# SparkFun_AST-CAN485.net
KiCad netlist of a schematic drawn in EAGLE
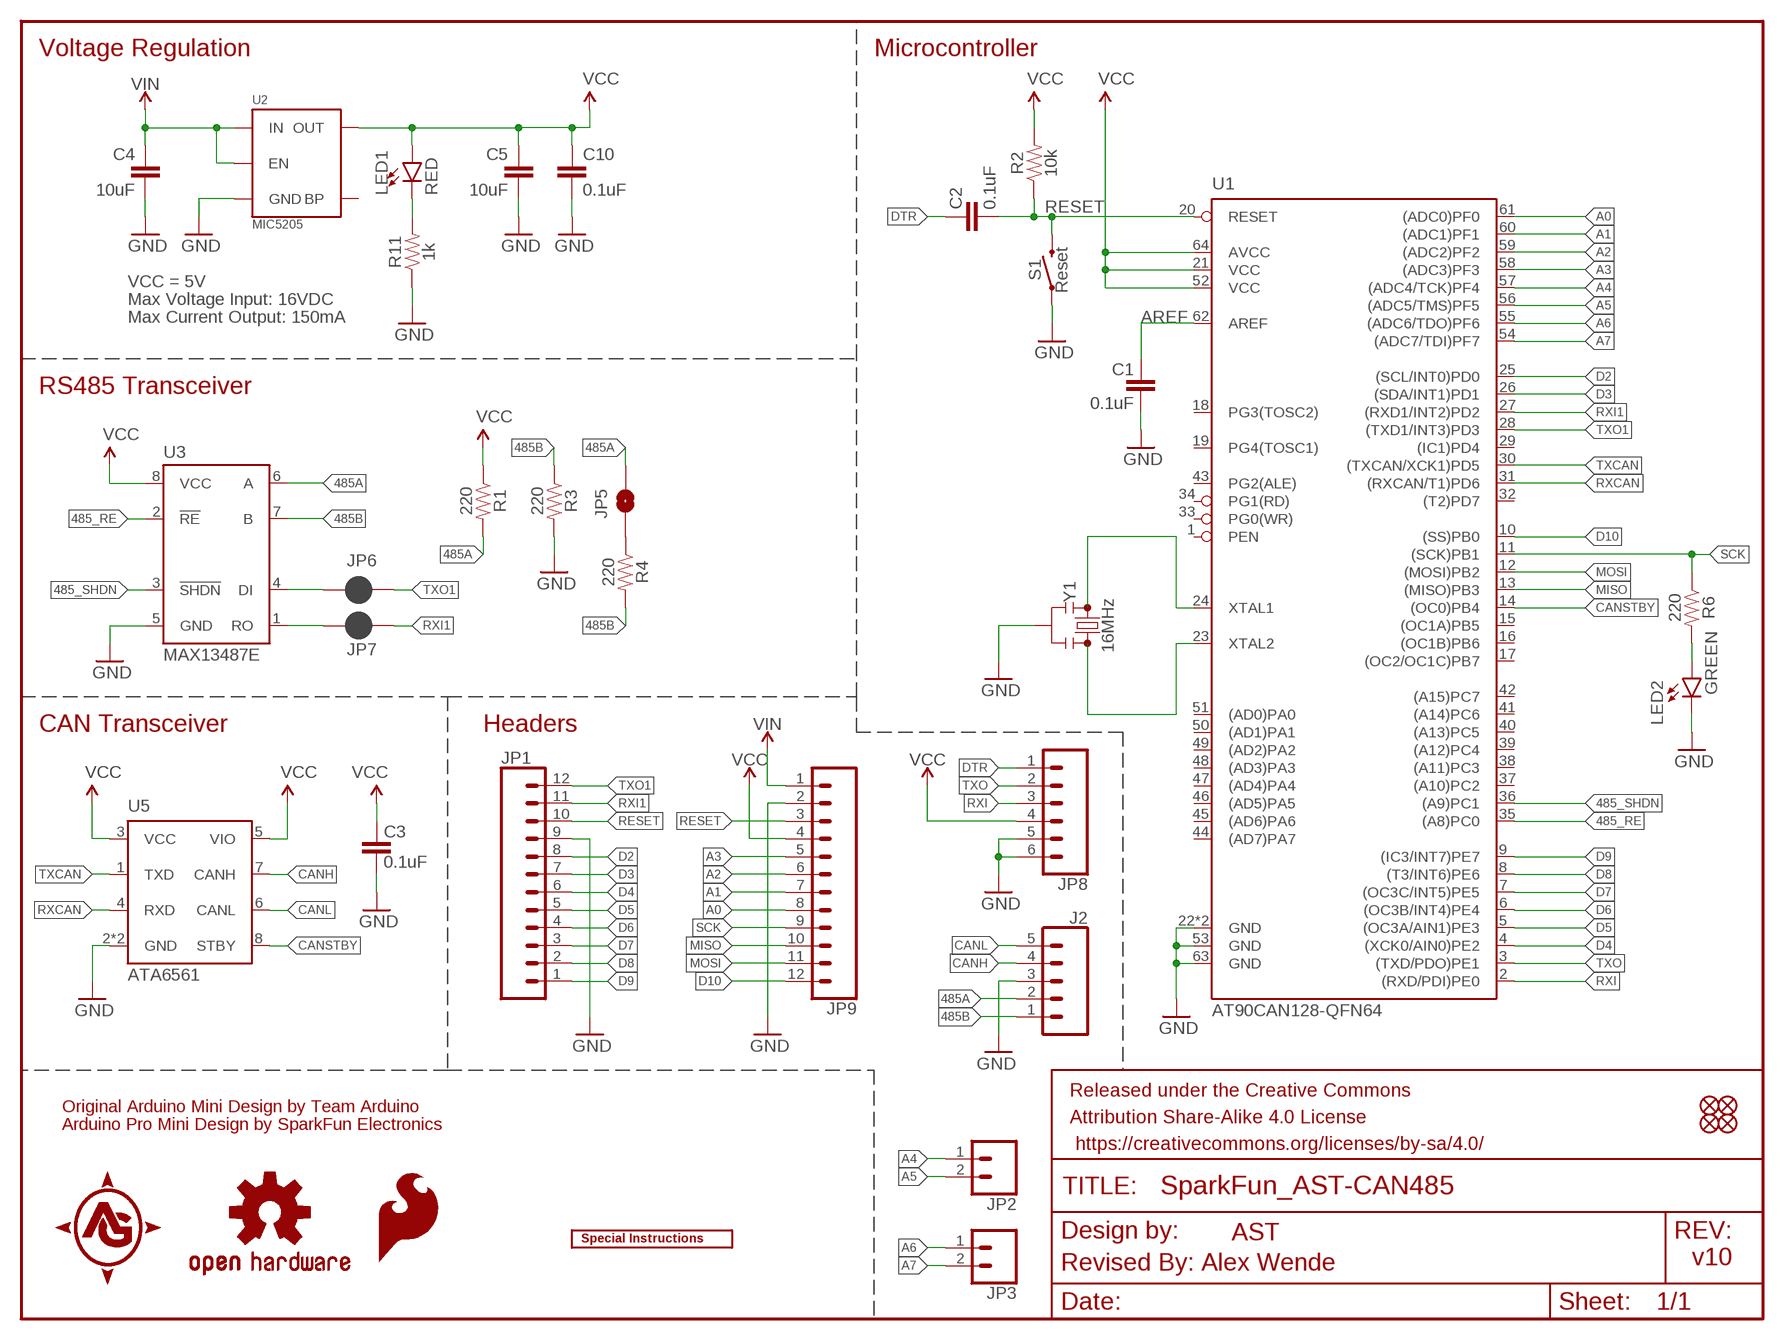
[diagram p0: schematic, sheet 1]

(export (version "E")
  (design (tool "Eeschema 10.0.6"))
  (components
    (comp (ref "C1")
      (value "0.1uF")
      (footprint "eagle-import:0402")
      (libsource (lib "eagle-import") (part "0.1UF-0402-16V-10%"))
    )
    (comp (ref "C2")
      (value "0.1uF")
      (footprint "eagle-import:0402")
      (libsource (lib "eagle-import") (part "0.1UF-0402-16V-10%"))
    )
    (comp (ref "C3")
      (value "0.1uF")
      (footprint "eagle-import:0402")
      (libsource (lib "eagle-import") (part "0.1UF-0402-16V-10%"))
    )
    (comp (ref "C4")
      (value "10uF")
      (footprint "eagle-import:1210")
      (libsource (lib "eagle-import") (part "10UF-1210-50V-20%"))
    )
    (comp (ref "C5")
      (value "10uF")
      (footprint "eagle-import:1210")
      (libsource (lib "eagle-import") (part "10UF-1210-50V-20%"))
    )
    (comp (ref "C10")
      (value "0.1uF")
      (footprint "eagle-import:0402")
      (libsource (lib "eagle-import") (part "0.1UF-0402-16V-10%"))
    )
    (comp (ref "FD1")
      (value "FIDUCIALUFIDUCIAL")
      (footprint "eagle-import:FIDUCIAL-MICRO")
      (libsource (lib "eagle-import") (part "FIDUCIALUFIDUCIAL"))
    )
    (comp (ref "FD2")
      (value "FIDUCIALUFIDUCIAL")
      (footprint "eagle-import:FIDUCIAL-MICRO")
      (libsource (lib "eagle-import") (part "FIDUCIALUFIDUCIAL"))
    )
    (comp (ref "FD3")
      (value "FIDUCIALUFIDUCIAL")
      (footprint "eagle-import:FIDUCIAL-MICRO")
      (libsource (lib "eagle-import") (part "FIDUCIALUFIDUCIAL"))
    )
    (comp (ref "FD4")
      (value "FIDUCIALUFIDUCIAL")
      (footprint "eagle-import:FIDUCIAL-MICRO")
      (libsource (lib "eagle-import") (part "FIDUCIALUFIDUCIAL"))
    )
    (comp (ref "FRAME1")
      (value "FRAME-LETTER")
      (footprint "eagle-import:CREATIVE_COMMONS")
      (libsource (lib "eagle-import") (part "FRAME-LETTER"))
    )
    (comp (ref "J2")
      (value "CONN_05NO_SILK")
      (footprint "eagle-import:1X05_NO_SILK")
      (libsource (lib "eagle-import") (part "CONN_05NO_SILK"))
    )
    (comp (ref "JP1")
      (value "CONN_12NO_SILK")
      (footprint "eagle-import:1X12_NO_SILK")
      (libsource (lib "eagle-import") (part "CONN_12NO_SILK"))
    )
    (comp (ref "JP2")
      (value "CONN_021X02_NO_SILK")
      (footprint "eagle-import:1X02_NO_SILK")
      (libsource (lib "eagle-import") (part "CONN_021X02_NO_SILK"))
    )
    (comp (ref "JP3")
      (value "CONN_021X02_NO_SILK")
      (footprint "eagle-import:1X02_NO_SILK")
      (libsource (lib "eagle-import") (part "CONN_021X02_NO_SILK"))
    )
    (comp (ref "JP5")
      (value "JUMPER-PAD-2-NO")
      (footprint "eagle-import:PAD-JUMPER-2-NO_NO_SILK")
      (libsource (lib "eagle-import") (part "JUMPER-PAD-2-NO"))
    )
    (comp (ref "JP6")
      (value "JUMPER-SMT_2_NC_PASTE_NO-SILK")
      (footprint "eagle-import:SMT-JUMPER_2_NC_PASTE_NO-SILK")
      (libsource (lib "eagle-import") (part "JUMPER-SMT_2_NC_PASTE_NO-SILK"))
    )
    (comp (ref "JP7")
      (value "JUMPER-SMT_2_NC_PASTE_NO-SILK")
      (footprint "eagle-import:SMT-JUMPER_2_NC_PASTE_NO-SILK")
      (libsource (lib "eagle-import") (part "JUMPER-SMT_2_NC_PASTE_NO-SILK"))
    )
    (comp (ref "JP8")
      (value "CONN_06NO_SILK_NO_POP")
      (footprint "eagle-import:1X06_NO_SILK")
      (libsource (lib "eagle-import") (part "CONN_06NO_SILK_NO_POP"))
    )
    (comp (ref "JP9")
      (value "CONN_12NO_SILK")
      (footprint "eagle-import:1X12_NO_SILK")
      (libsource (lib "eagle-import") (part "CONN_12NO_SILK"))
    )
    (comp (ref "LED1")
      (value "RED")
      (footprint "eagle-import:LED-0603")
      (libsource (lib "eagle-import") (part "LED-RED0603"))
    )
    (comp (ref "LED2")
      (value "GREEN")
      (footprint "eagle-import:LED-0603")
      (libsource (lib "eagle-import") (part "LED-GREEN0603"))
    )
    (comp (ref "LOGO1")
      (value "OSHW-LOGOMINI")
      (footprint "eagle-import:OSHW-LOGO-MINI")
      (libsource (lib "eagle-import") (part "OSHW-LOGOMINI"))
    )
    (comp (ref "LOGO2")
      (value "SFE_LOGO_FLAME0.05_INCH")
      (footprint "eagle-import:SFE_LOGO_FLAME_.05")
      (libsource (lib "eagle-import") (part "SFE_LOGO_FLAME0.05_INCH"))
    )
    (comp (ref "R1")
      (value "220")
      (footprint "eagle-import:0603")
      (libsource (lib "eagle-import") (part "220OHM-0603-1/10W-1%"))
    )
    (comp (ref "R2")
      (value "10k")
      (footprint "eagle-import:0603")
      (libsource (lib "eagle-import") (part "10KOHM-0603-1/10W-1%"))
    )
    (comp (ref "R3")
      (value "220")
      (footprint "eagle-import:0603")
      (libsource (lib "eagle-import") (part "220OHM-0603-1/10W-1%"))
    )
    (comp (ref "R4")
      (value "220")
      (footprint "eagle-import:0603")
      (libsource (lib "eagle-import") (part "220OHM-0603-1/10W-1%"))
    )
    (comp (ref "R6")
      (value "220")
      (footprint "eagle-import:0603")
      (libsource (lib "eagle-import") (part "220OHM-0603-1/10W-1%"))
    )
    (comp (ref "R11")
      (value "1k")
      (footprint "eagle-import:0603")
      (libsource (lib "eagle-import") (part "1KOHM-0603-1/10W-1%"))
    )
    (comp (ref "S1")
      (value "Reset")
      (footprint "eagle-import:TACTILE_SWITCH_SMD_4.6X2.8MM")
      (libsource (lib "eagle-import") (part "MOMENTARY-SWITCH-SPST-SMD-4.6X2.8MM"))
    )
    (comp (ref "U$1")
      (value "SPECIAL_INSTRUCTIONS-ORDERING")
      (footprint "eagle-import:ORDERING_INSTRUCTIONS")
      (libsource (lib "eagle-import") (part "SPECIAL_INSTRUCTIONS-ORDERING"))
    )
    (comp (ref "U1")
      (value "AT90CAN128-QFN64")
      (footprint "eagle-import:QFN-64")
      (libsource (lib "eagle-import") (part "AT90CAN128-QFN64"))
    )
    (comp (ref "U2")
      (value "MIC5205")
      (footprint "eagle-import:SOT23-5")
      (libsource (lib "eagle-import") (part "MIC5205"))
    )
    (comp (ref "U3")
      (value "MAX13487E")
      (footprint "eagle-import:SO08")
      (libsource (lib "eagle-import") (part "MAX13487E"))
    )
    (comp (ref "U5")
      (value "ATA6561")
      (footprint "eagle-import:DFN8")
      (libsource (lib "eagle-import") (part "ATA6561"))
    )
    (comp (ref "Y1")
      (value "16MHz")
      (footprint "eagle-import:RESONATOR-SMD-3.2X1.3(SLIM)")
      (libsource (lib "eagle-import") (part "RESONATOR-16MHZSMD_3.2X1.3_SLIM"))
    )
  )
  (nets
    (net (code "1") (name "/AREF") (class "Default")
      (node (ref "C1") (pin "2") (pinfunction "2_2") (pintype "passive"))
      (node (ref "U1") (pin "62") (pinfunction "AREF_62") (pintype "bidirectional"))
    )
    (net (code "2") (name "485A") (class "Default")
      (node (ref "J2") (pin "2") (pinfunction "2_2") (pintype "passive"))
      (node (ref "JP5") (pin "2") (pinfunction "2_2") (pintype "passive"))
      (node (ref "R1") (pin "2") (pinfunction "2_2") (pintype "passive"))
      (node (ref "U3") (pin "6") (pinfunction "A_6") (pintype "bidirectional"))
    )
    (net (code "3") (name "485B") (class "Default")
      (node (ref "J2") (pin "1") (pinfunction "1_1") (pintype "passive"))
      (node (ref "R3") (pin "1") (pinfunction "1_1") (pintype "passive"))
      (node (ref "R4") (pin "2") (pinfunction "2_2") (pintype "passive"))
      (node (ref "U3") (pin "7") (pinfunction "B_7") (pintype "bidirectional"))
    )
    (net (code "4") (name "485_RE") (class "Default")
      (node (ref "U1") (pin "35") (pinfunction "(A8)PC0_35") (pintype "bidirectional"))
      (node (ref "U3") (pin "2") (pinfunction "~{RE}_2") (pintype "bidirectional"))
    )
    (net (code "5") (name "485_SHDN") (class "Default")
      (node (ref "U1") (pin "36") (pinfunction "(A9)PC1_36") (pintype "bidirectional"))
      (node (ref "U3") (pin "3") (pinfunction "~{SHDN}_3") (pintype "bidirectional"))
    )
    (net (code "6") (name "A0") (class "Default")
      (node (ref "JP9") (pin "8") (pinfunction "8_8") (pintype "passive"))
      (node (ref "U1") (pin "61") (pinfunction "(ADC0)PF0_61") (pintype "bidirectional"))
    )
    (net (code "7") (name "A1") (class "Default")
      (node (ref "JP9") (pin "7") (pinfunction "7_7") (pintype "passive"))
      (node (ref "U1") (pin "60") (pinfunction "(ADC1)PF1_60") (pintype "bidirectional"))
    )
    (net (code "8") (name "A2") (class "Default")
      (node (ref "JP9") (pin "6") (pinfunction "6_6") (pintype "passive"))
      (node (ref "U1") (pin "59") (pinfunction "(ADC2)PF2_59") (pintype "bidirectional"))
    )
    (net (code "9") (name "A3") (class "Default")
      (node (ref "JP9") (pin "5") (pinfunction "5_5") (pintype "passive"))
      (node (ref "U1") (pin "58") (pinfunction "(ADC3)PF3_58") (pintype "bidirectional"))
    )
    (net (code "10") (name "A4") (class "Default")
      (node (ref "JP2") (pin "1") (pinfunction "1_1") (pintype "passive"))
      (node (ref "U1") (pin "57") (pinfunction "(ADC4/TCK)PF4_57") (pintype "bidirectional"))
    )
    (net (code "11") (name "A5") (class "Default")
      (node (ref "JP2") (pin "2") (pinfunction "2_2") (pintype "passive"))
      (node (ref "U1") (pin "56") (pinfunction "(ADC5/TMS)PF5_56") (pintype "bidirectional"))
    )
    (net (code "12") (name "A6") (class "Default")
      (node (ref "JP3") (pin "1") (pinfunction "1_1") (pintype "passive"))
      (node (ref "U1") (pin "55") (pinfunction "(ADC6/TDO)PF6_55") (pintype "bidirectional"))
    )
    (net (code "13") (name "A7") (class "Default")
      (node (ref "JP3") (pin "2") (pinfunction "2_2") (pintype "passive"))
      (node (ref "U1") (pin "54") (pinfunction "(ADC7/TDI)PF7_54") (pintype "bidirectional"))
    )
    (net (code "14") (name "CANH") (class "Default")
      (node (ref "J2") (pin "4") (pinfunction "4_4") (pintype "passive"))
      (node (ref "U5") (pin "7") (pinfunction "CANH_7") (pintype "bidirectional"))
    )
    (net (code "15") (name "CANL") (class "Default")
      (node (ref "J2") (pin "5") (pinfunction "5_5") (pintype "passive"))
      (node (ref "U5") (pin "6") (pinfunction "CANL_6") (pintype "bidirectional"))
    )
    (net (code "16") (name "CANSTBY") (class "Default")
      (node (ref "U1") (pin "14") (pinfunction "(OC0)PB4_14") (pintype "bidirectional"))
      (node (ref "U5") (pin "8") (pinfunction "STBY_8") (pintype "bidirectional"))
    )
    (net (code "17") (name "D2") (class "Default")
      (node (ref "JP1") (pin "8") (pinfunction "8_8") (pintype "passive"))
      (node (ref "U1") (pin "25") (pinfunction "(SCL/INT0)PD0_25") (pintype "bidirectional"))
    )
    (net (code "18") (name "D3") (class "Default")
      (node (ref "JP1") (pin "7") (pinfunction "7_7") (pintype "passive"))
      (node (ref "U1") (pin "26") (pinfunction "(SDA/INT1)PD1_26") (pintype "bidirectional"))
    )
    (net (code "19") (name "D4") (class "Default")
      (node (ref "JP1") (pin "6") (pinfunction "6_6") (pintype "passive"))
      (node (ref "U1") (pin "4") (pinfunction "(XCK0/AIN0)PE2_4") (pintype "bidirectional"))
    )
    (net (code "20") (name "D5") (class "Default")
      (node (ref "JP1") (pin "5") (pinfunction "5_5") (pintype "passive"))
      (node (ref "U1") (pin "5") (pinfunction "(OC3A/AIN1)PE3_5") (pintype "bidirectional"))
    )
    (net (code "21") (name "D6") (class "Default")
      (node (ref "JP1") (pin "4") (pinfunction "4_4") (pintype "passive"))
      (node (ref "U1") (pin "6") (pinfunction "(OC3B/INT4)PE4_6") (pintype "bidirectional"))
    )
    (net (code "22") (name "D7") (class "Default")
      (node (ref "JP1") (pin "3") (pinfunction "3_3") (pintype "passive"))
      (node (ref "U1") (pin "7") (pinfunction "(OC3C/INT5)PE5_7") (pintype "bidirectional"))
    )
    (net (code "23") (name "D8") (class "Default")
      (node (ref "JP1") (pin "2") (pinfunction "2_2") (pintype "passive"))
      (node (ref "U1") (pin "8") (pinfunction "(T3/INT6)PE6_8") (pintype "bidirectional"))
    )
    (net (code "24") (name "D9") (class "Default")
      (node (ref "JP1") (pin "1") (pinfunction "1_1") (pintype "passive"))
      (node (ref "U1") (pin "9") (pinfunction "(IC3/INT7)PE7_9") (pintype "bidirectional"))
    )
    (net (code "25") (name "D10") (class "Default")
      (node (ref "JP9") (pin "12") (pinfunction "12_12") (pintype "passive"))
      (node (ref "U1") (pin "10") (pinfunction "(SS)PB0_10") (pintype "bidirectional"))
    )
    (net (code "26") (name "DTR") (class "Default")
      (node (ref "C2") (pin "2") (pinfunction "2_2") (pintype "passive"))
      (node (ref "JP8") (pin "1") (pinfunction "1_1") (pintype "passive"))
    )
    (net (code "27") (name "GND") (class "Default")
      (node (ref "C1") (pin "1") (pinfunction "1_1") (pintype "passive"))
      (node (ref "C10") (pin "2") (pinfunction "2_2") (pintype "passive"))
      (node (ref "C3") (pin "1") (pinfunction "1_1") (pintype "passive"))
      (node (ref "C4") (pin "2") (pinfunction "2_2") (pintype "passive"))
      (node (ref "C5") (pin "2") (pinfunction "2_2") (pintype "passive"))
      (node (ref "J2") (pin "3") (pinfunction "3_3") (pintype "passive"))
      (node (ref "JP1") (pin "9") (pinfunction "9_9") (pintype "passive"))
      (node (ref "JP8") (pin "5") (pinfunction "5_5") (pintype "passive"))
      (node (ref "JP8") (pin "6") (pinfunction "6_6") (pintype "passive"))
      (node (ref "JP9") (pin "2") (pinfunction "2_2") (pintype "passive"))
      (node (ref "LED2") (pin "C") (pinfunction "C_C") (pintype "passive"))
      (node (ref "R11") (pin "1") (pinfunction "1_1") (pintype "passive"))
      (node (ref "R3") (pin "2") (pinfunction "2_2") (pintype "passive"))
      (node (ref "S1") (pin "1") (pinfunction "1_1") (pintype "passive"))
      (node (ref "S1") (pin "2") (pinfunction "1_2") (pintype "passive"))
      (node (ref "U1") (pin "22") (pinfunction "GND_22") (pintype "bidirectional"))
      (node (ref "U1") (pin "53") (pinfunction "GND_53") (pintype "bidirectional"))
      (node (ref "U1") (pin "63") (pinfunction "GND_63") (pintype "bidirectional"))
      (node (ref "U1") (pin "65") (pinfunction "GND_65") (pintype "bidirectional"))
      (node (ref "U2") (pin "2") (pinfunction "GND_2") (pintype "bidirectional"))
      (node (ref "U3") (pin "5") (pinfunction "GND_5") (pintype "bidirectional"))
      (node (ref "U5") (pin "2") (pinfunction "GND_2") (pintype "bidirectional"))
      (node (ref "U5") (pin "9") (pinfunction "GND_9") (pintype "bidirectional"))
      (node (ref "Y1") (pin "2") (pinfunction "2_2") (pintype "passive"))
    )
    (net (code "28") (name "MISO") (class "Default")
      (node (ref "JP9") (pin "10") (pinfunction "10_10") (pintype "passive"))
      (node (ref "U1") (pin "13") (pinfunction "(MISO)PB3_13") (pintype "bidirectional"))
    )
    (net (code "29") (name "MOSI") (class "Default")
      (node (ref "JP9") (pin "11") (pinfunction "11_11") (pintype "passive"))
      (node (ref "U1") (pin "12") (pinfunction "(MOSI)PB2_12") (pintype "bidirectional"))
    )
    (net (code "30") (name "Net-(JP5-Pad1)") (class "Default")
      (node (ref "JP5") (pin "1") (pinfunction "1_1") (pintype "passive"))
      (node (ref "R4") (pin "1") (pinfunction "1_1") (pintype "passive"))
    )
    (net (code "31") (name "Net-(LED1-PadC)") (class "Default")
      (node (ref "LED1") (pin "C") (pinfunction "C_C") (pintype "passive"))
      (node (ref "R11") (pin "2") (pinfunction "2_2") (pintype "passive"))
    )
    (net (code "32") (name "Net-(LED2-PadA)") (class "Default")
      (node (ref "LED2") (pin "A") (pinfunction "A_A") (pintype "passive"))
      (node (ref "R6") (pin "2") (pinfunction "2_2") (pintype "passive"))
    )
    (net (code "33") (name "Net-(U1-XTAL1)") (class "Default")
      (node (ref "U1") (pin "24") (pinfunction "XTAL1_24") (pintype "bidirectional"))
      (node (ref "Y1") (pin "1") (pinfunction "1_1") (pintype "passive"))
    )
    (net (code "34") (name "Net-(U1-XTAL2)") (class "Default")
      (node (ref "U1") (pin "23") (pinfunction "XTAL2_23") (pintype "bidirectional"))
      (node (ref "Y1") (pin "3") (pinfunction "3_3") (pintype "passive"))
    )
    (net (code "35") (name "Net-(U3-DI)") (class "Default")
      (node (ref "JP6") (pin "2") (pinfunction "2_2") (pintype "passive"))
      (node (ref "U3") (pin "4") (pinfunction "DI_4") (pintype "bidirectional"))
    )
    (net (code "36") (name "Net-(U3-RO)") (class "Default")
      (node (ref "JP7") (pin "2") (pinfunction "2_2") (pintype "passive"))
      (node (ref "U3") (pin "1") (pinfunction "RO_1") (pintype "bidirectional"))
    )
    (net (code "37") (name "RESET") (class "Default")
      (node (ref "C2") (pin "1") (pinfunction "1_1") (pintype "passive"))
      (node (ref "JP1") (pin "10") (pinfunction "10_10") (pintype "passive"))
      (node (ref "JP9") (pin "3") (pinfunction "3_3") (pintype "passive"))
      (node (ref "R2") (pin "1") (pinfunction "1_1") (pintype "passive"))
      (node (ref "S1") (pin "3") (pinfunction "2_3") (pintype "passive"))
      (node (ref "S1") (pin "4") (pinfunction "2_4") (pintype "passive"))
      (node (ref "U1") (pin "20") (pinfunction "RESET_20") (pintype "bidirectional"))
    )
    (net (code "38") (name "RXCAN") (class "Default")
      (node (ref "U1") (pin "31") (pinfunction "(RXCAN/T1)PD6_31") (pintype "bidirectional"))
      (node (ref "U5") (pin "4") (pinfunction "RXD_4") (pintype "bidirectional"))
    )
    (net (code "39") (name "RXI") (class "Default")
      (node (ref "JP8") (pin "3") (pinfunction "3_3") (pintype "passive"))
      (node (ref "U1") (pin "2") (pinfunction "(RXD/PDI)PE0_2") (pintype "bidirectional"))
    )
    (net (code "40") (name "RXI1") (class "Default")
      (node (ref "JP1") (pin "11") (pinfunction "11_11") (pintype "passive"))
      (node (ref "JP7") (pin "1") (pinfunction "1_1") (pintype "passive"))
      (node (ref "U1") (pin "27") (pinfunction "(RXD1/INT2)PD2_27") (pintype "bidirectional"))
    )
    (net (code "41") (name "SCK") (class "Default")
      (node (ref "JP9") (pin "9") (pinfunction "9_9") (pintype "passive"))
      (node (ref "R6") (pin "1") (pinfunction "1_1") (pintype "passive"))
      (node (ref "U1") (pin "11") (pinfunction "(SCK)PB1_11") (pintype "bidirectional"))
    )
    (net (code "42") (name "TXCAN") (class "Default")
      (node (ref "U1") (pin "30") (pinfunction "(TXCAN/XCK1)PD5_30") (pintype "bidirectional"))
      (node (ref "U5") (pin "1") (pinfunction "TXD_1") (pintype "bidirectional"))
    )
    (net (code "43") (name "TXO") (class "Default")
      (node (ref "JP8") (pin "2") (pinfunction "2_2") (pintype "passive"))
      (node (ref "U1") (pin "3") (pinfunction "(TXD/PDO)PE1_3") (pintype "bidirectional"))
    )
    (net (code "44") (name "TXO1") (class "Default")
      (node (ref "JP1") (pin "12") (pinfunction "12_12") (pintype "passive"))
      (node (ref "JP6") (pin "1") (pinfunction "1_1") (pintype "passive"))
      (node (ref "U1") (pin "28") (pinfunction "(TXD1/INT3)PD3_28") (pintype "bidirectional"))
    )
    (net (code "45") (name "VCC") (class "Default")
      (node (ref "C10") (pin "1") (pinfunction "1_1") (pintype "passive"))
      (node (ref "C3") (pin "2") (pinfunction "2_2") (pintype "passive"))
      (node (ref "C5") (pin "1") (pinfunction "1_1") (pintype "passive"))
      (node (ref "JP8") (pin "4") (pinfunction "4_4") (pintype "passive"))
      (node (ref "JP9") (pin "4") (pinfunction "4_4") (pintype "passive"))
      (node (ref "LED1") (pin "A") (pinfunction "A_A") (pintype "passive"))
      (node (ref "R1") (pin "1") (pinfunction "1_1") (pintype "passive"))
      (node (ref "R2") (pin "2") (pinfunction "2_2") (pintype "passive"))
      (node (ref "U1") (pin "21") (pinfunction "VCC_21") (pintype "bidirectional"))
      (node (ref "U1") (pin "52") (pinfunction "VCC_52") (pintype "bidirectional"))
      (node (ref "U1") (pin "64") (pinfunction "AVCC_64") (pintype "bidirectional"))
      (node (ref "U2") (pin "5") (pinfunction "OUT_5") (pintype "bidirectional"))
      (node (ref "U3") (pin "8") (pinfunction "VCC_8") (pintype "bidirectional"))
      (node (ref "U5") (pin "3") (pinfunction "VCC_3") (pintype "bidirectional"))
      (node (ref "U5") (pin "5") (pinfunction "VIO_5") (pintype "bidirectional"))
    )
    (net (code "46") (name "VIN") (class "Default")
      (node (ref "C4") (pin "1") (pinfunction "1_1") (pintype "passive"))
      (node (ref "JP9") (pin "1") (pinfunction "1_1") (pintype "passive"))
      (node (ref "U2") (pin "1") (pinfunction "IN_1") (pintype "bidirectional"))
      (node (ref "U2") (pin "3") (pinfunction "EN_3") (pintype "bidirectional"))
    )
    (net (code "47") (name "unconnected-(U1-(A10)PC2-Pad37)") (class "Default")
      (node (ref "U1") (pin "37") (pinfunction "(A10)PC2_37") (pintype "bidirectional"))
    )
    (net (code "48") (name "unconnected-(U1-(A11)PC3-Pad38)") (class "Default")
      (node (ref "U1") (pin "38") (pinfunction "(A11)PC3_38") (pintype "bidirectional"))
    )
    (net (code "49") (name "unconnected-(U1-(A12)PC4-Pad39)") (class "Default")
      (node (ref "U1") (pin "39") (pinfunction "(A12)PC4_39") (pintype "bidirectional"))
    )
    (net (code "50") (name "unconnected-(U1-(A13)PC5-Pad40)") (class "Default")
      (node (ref "U1") (pin "40") (pinfunction "(A13)PC5_40") (pintype "bidirectional"))
    )
    (net (code "51") (name "unconnected-(U1-(A14)PC6-Pad41)") (class "Default")
      (node (ref "U1") (pin "41") (pinfunction "(A14)PC6_41") (pintype "bidirectional"))
    )
    (net (code "52") (name "unconnected-(U1-(A15)PC7-Pad42)") (class "Default")
      (node (ref "U1") (pin "42") (pinfunction "(A15)PC7_42") (pintype "bidirectional"))
    )
    (net (code "53") (name "unconnected-(U1-(AD0)PA0-Pad51)") (class "Default")
      (node (ref "U1") (pin "51") (pinfunction "(AD0)PA0_51") (pintype "bidirectional"))
    )
    (net (code "54") (name "unconnected-(U1-(AD1)PA1-Pad50)") (class "Default")
      (node (ref "U1") (pin "50") (pinfunction "(AD1)PA1_50") (pintype "bidirectional"))
    )
    (net (code "55") (name "unconnected-(U1-(AD2)PA2-Pad49)") (class "Default")
      (node (ref "U1") (pin "49") (pinfunction "(AD2)PA2_49") (pintype "bidirectional"))
    )
    (net (code "56") (name "unconnected-(U1-(AD3)PA3-Pad48)") (class "Default")
      (node (ref "U1") (pin "48") (pinfunction "(AD3)PA3_48") (pintype "bidirectional"))
    )
    (net (code "57") (name "unconnected-(U1-(AD4)PA4-Pad47)") (class "Default")
      (node (ref "U1") (pin "47") (pinfunction "(AD4)PA4_47") (pintype "bidirectional"))
    )
    (net (code "58") (name "unconnected-(U1-(AD5)PA5-Pad46)") (class "Default")
      (node (ref "U1") (pin "46") (pinfunction "(AD5)PA5_46") (pintype "bidirectional"))
    )
    (net (code "59") (name "unconnected-(U1-(AD6)PA6-Pad45)") (class "Default")
      (node (ref "U1") (pin "45") (pinfunction "(AD6)PA6_45") (pintype "bidirectional"))
    )
    (net (code "60") (name "unconnected-(U1-(AD7)PA7-Pad44)") (class "Default")
      (node (ref "U1") (pin "44") (pinfunction "(AD7)PA7_44") (pintype "bidirectional"))
    )
    (net (code "61") (name "unconnected-(U1-(IC1)PD4-Pad29)") (class "Default")
      (node (ref "U1") (pin "29") (pinfunction "(IC1)PD4_29") (pintype "bidirectional"))
    )
    (net (code "62") (name "unconnected-(U1-(OC1A)PB5-Pad15)") (class "Default")
      (node (ref "U1") (pin "15") (pinfunction "(OC1A)PB5_15") (pintype "bidirectional"))
    )
    (net (code "63") (name "unconnected-(U1-(OC1B)PB6-Pad16)") (class "Default")
      (node (ref "U1") (pin "16") (pinfunction "(OC1B)PB6_16") (pintype "bidirectional"))
    )
    (net (code "64") (name "unconnected-(U1-(OC2{slash}OC1C)PB7-Pad17)") (class "Default")
      (node (ref "U1") (pin "17") (pinfunction "(OC2/OC1C)PB7_17") (pintype "bidirectional"))
    )
    (net (code "65") (name "unconnected-(U1-(T2)PD7-Pad32)") (class "Default")
      (node (ref "U1") (pin "32") (pinfunction "(T2)PD7_32") (pintype "bidirectional"))
    )
    (net (code "66") (name "unconnected-(U1-PEN-Pad1)") (class "Default")
      (node (ref "U1") (pin "1") (pinfunction "PEN_1") (pintype "bidirectional"))
    )
    (net (code "67") (name "unconnected-(U1-PG0(WR)-Pad33)") (class "Default")
      (node (ref "U1") (pin "33") (pinfunction "PG0(WR)_33") (pintype "bidirectional"))
    )
    (net (code "68") (name "unconnected-(U1-PG1(RD)-Pad34)") (class "Default")
      (node (ref "U1") (pin "34") (pinfunction "PG1(RD)_34") (pintype "bidirectional"))
    )
    (net (code "69") (name "unconnected-(U1-PG2(ALE)-Pad43)") (class "Default")
      (node (ref "U1") (pin "43") (pinfunction "PG2(ALE)_43") (pintype "bidirectional"))
    )
    (net (code "70") (name "unconnected-(U1-PG3(TOSC2)-Pad18)") (class "Default")
      (node (ref "U1") (pin "18") (pinfunction "PG3(TOSC2)_18") (pintype "bidirectional"))
    )
    (net (code "71") (name "unconnected-(U1-PG4(TOSC1)-Pad19)") (class "Default")
      (node (ref "U1") (pin "19") (pinfunction "PG4(TOSC1)_19") (pintype "bidirectional"))
    )
    (net (code "72") (name "unconnected-(U2-BP-Pad4)") (class "Default")
      (node (ref "U2") (pin "4") (pinfunction "BP_4") (pintype "bidirectional"))
    )
  )
)
